# BREAKER_BOARD_FOR_TLC5951.net
KiCad netlist of a schematic drawn in EAGLE
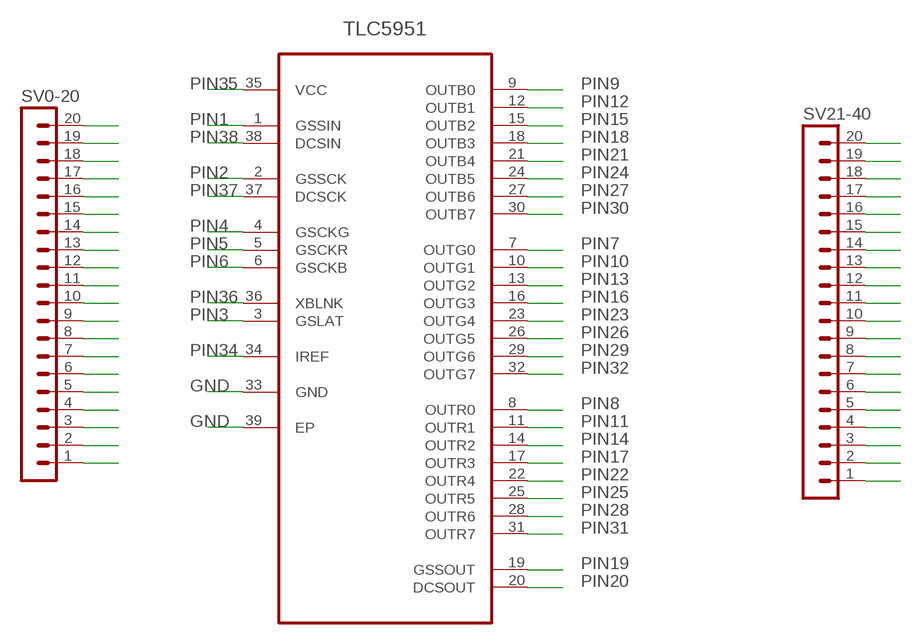
[diagram p0: schematic, sheet 1]

(export (version "E")
  (design (tool "Eeschema 10.0.6"))
  (components
    (comp (ref "SV0-20")
      (value "MA20-1")
      (footprint "eagle-import:MA20-1")
      (libsource (lib "eagle-import") (part "MA20-1"))
    )
    (comp (ref "SV21-40")
      (value "MA20-1")
      (footprint "eagle-import:MA20-1")
      (libsource (lib "eagle-import") (part "MA20-1"))
    )
    (comp (ref "TLC5951")
      (value "TLC5951DAP")
      (footprint "eagle-import:SOP65P810X120-39N")
      (libsource (lib "eagle-import") (part "TLC5951DAP"))
    )
  )
  (nets
    (net (code "1") (name "/GND") (class "Default")
      (node (ref "SV0-20") (pin "20") (pinfunction "20_20") (pintype "passive"))
      (node (ref "TLC5951") (pin "33") (pinfunction "GND_33") (pintype "passive"))
      (node (ref "TLC5951") (pin "39") (pinfunction "EP_39") (pintype "passive"))
    )
    (net (code "2") (name "/PIN1") (class "Default")
      (node (ref "SV0-20") (pin "1") (pinfunction "1_1") (pintype "passive"))
      (node (ref "TLC5951") (pin "1") (pinfunction "GSSIN_1") (pintype "input"))
    )
    (net (code "3") (name "/PIN2") (class "Default")
      (node (ref "SV0-20") (pin "2") (pinfunction "2_2") (pintype "passive"))
      (node (ref "TLC5951") (pin "2") (pinfunction "GSSCK_2") (pintype "input"))
    )
    (net (code "4") (name "/PIN3") (class "Default")
      (node (ref "SV0-20") (pin "3") (pinfunction "3_3") (pintype "passive"))
      (node (ref "TLC5951") (pin "3") (pinfunction "GSLAT_3") (pintype "input"))
    )
    (net (code "5") (name "/PIN4") (class "Default")
      (node (ref "SV0-20") (pin "4") (pinfunction "4_4") (pintype "passive"))
      (node (ref "TLC5951") (pin "4") (pinfunction "GSCKG_4") (pintype "input"))
    )
    (net (code "6") (name "/PIN5") (class "Default")
      (node (ref "SV0-20") (pin "5") (pinfunction "5_5") (pintype "passive"))
      (node (ref "TLC5951") (pin "5") (pinfunction "GSCKR_5") (pintype "input"))
    )
    (net (code "7") (name "/PIN6") (class "Default")
      (node (ref "SV0-20") (pin "6") (pinfunction "6_6") (pintype "passive"))
      (node (ref "TLC5951") (pin "6") (pinfunction "GSCKB_6") (pintype "input"))
    )
    (net (code "8") (name "/PIN7") (class "Default")
      (node (ref "SV0-20") (pin "7") (pinfunction "7_7") (pintype "passive"))
      (node (ref "TLC5951") (pin "7") (pinfunction "OUTG0_7") (pintype "output"))
    )
    (net (code "9") (name "/PIN8") (class "Default")
      (node (ref "SV0-20") (pin "8") (pinfunction "8_8") (pintype "passive"))
      (node (ref "TLC5951") (pin "8") (pinfunction "OUTR0_8") (pintype "output"))
    )
    (net (code "10") (name "/PIN9") (class "Default")
      (node (ref "SV0-20") (pin "9") (pinfunction "9_9") (pintype "passive"))
      (node (ref "TLC5951") (pin "9") (pinfunction "OUTB0_9") (pintype "output"))
    )
    (net (code "11") (name "/PIN10") (class "Default")
      (node (ref "SV0-20") (pin "10") (pinfunction "10_10") (pintype "passive"))
      (node (ref "TLC5951") (pin "10") (pinfunction "OUTG1_10") (pintype "output"))
    )
    (net (code "12") (name "/PIN11") (class "Default")
      (node (ref "SV0-20") (pin "11") (pinfunction "11_11") (pintype "passive"))
      (node (ref "TLC5951") (pin "11") (pinfunction "OUTR1_11") (pintype "output"))
    )
    (net (code "13") (name "/PIN12") (class "Default")
      (node (ref "SV0-20") (pin "12") (pinfunction "12_12") (pintype "passive"))
      (node (ref "TLC5951") (pin "12") (pinfunction "OUTB1_12") (pintype "output"))
    )
    (net (code "14") (name "/PIN13") (class "Default")
      (node (ref "SV0-20") (pin "13") (pinfunction "13_13") (pintype "passive"))
      (node (ref "TLC5951") (pin "13") (pinfunction "OUTG2_13") (pintype "output"))
    )
    (net (code "15") (name "/PIN14") (class "Default")
      (node (ref "SV0-20") (pin "14") (pinfunction "14_14") (pintype "passive"))
      (node (ref "TLC5951") (pin "14") (pinfunction "OUTR2_14") (pintype "output"))
    )
    (net (code "16") (name "/PIN15") (class "Default")
      (node (ref "SV0-20") (pin "15") (pinfunction "15_15") (pintype "passive"))
      (node (ref "TLC5951") (pin "15") (pinfunction "OUTB2_15") (pintype "output"))
    )
    (net (code "17") (name "/PIN16") (class "Default")
      (node (ref "SV0-20") (pin "16") (pinfunction "16_16") (pintype "passive"))
      (node (ref "TLC5951") (pin "16") (pinfunction "OUTG3_16") (pintype "output"))
    )
    (net (code "18") (name "/PIN17") (class "Default")
      (node (ref "SV0-20") (pin "17") (pinfunction "17_17") (pintype "passive"))
      (node (ref "TLC5951") (pin "17") (pinfunction "OUTR3_17") (pintype "output"))
    )
    (net (code "19") (name "/PIN18") (class "Default")
      (node (ref "SV0-20") (pin "18") (pinfunction "18_18") (pintype "passive"))
      (node (ref "TLC5951") (pin "18") (pinfunction "OUTB3_18") (pintype "output"))
    )
    (net (code "20") (name "/PIN19") (class "Default")
      (node (ref "SV0-20") (pin "19") (pinfunction "19_19") (pintype "passive"))
      (node (ref "TLC5951") (pin "19") (pinfunction "GSSOUT_19") (pintype "output"))
    )
    (net (code "21") (name "/PIN20") (class "Default")
      (node (ref "SV21-40") (pin "19") (pinfunction "19_19") (pintype "passive"))
      (node (ref "TLC5951") (pin "20") (pinfunction "DCSOUT_20") (pintype "output"))
    )
    (net (code "22") (name "/PIN21") (class "Default")
      (node (ref "SV21-40") (pin "18") (pinfunction "18_18") (pintype "passive"))
      (node (ref "TLC5951") (pin "21") (pinfunction "OUTB4_21") (pintype "output"))
    )
    (net (code "23") (name "/PIN22") (class "Default")
      (node (ref "SV21-40") (pin "17") (pinfunction "17_17") (pintype "passive"))
      (node (ref "TLC5951") (pin "22") (pinfunction "OUTR4_22") (pintype "output"))
    )
    (net (code "24") (name "/PIN23") (class "Default")
      (node (ref "SV21-40") (pin "16") (pinfunction "16_16") (pintype "passive"))
      (node (ref "TLC5951") (pin "23") (pinfunction "OUTG4_23") (pintype "output"))
    )
    (net (code "25") (name "/PIN24") (class "Default")
      (node (ref "SV21-40") (pin "15") (pinfunction "15_15") (pintype "passive"))
      (node (ref "TLC5951") (pin "24") (pinfunction "OUTB5_24") (pintype "output"))
    )
    (net (code "26") (name "/PIN25") (class "Default")
      (node (ref "SV21-40") (pin "14") (pinfunction "14_14") (pintype "passive"))
      (node (ref "TLC5951") (pin "25") (pinfunction "OUTR5_25") (pintype "output"))
    )
    (net (code "27") (name "/PIN26") (class "Default")
      (node (ref "SV21-40") (pin "13") (pinfunction "13_13") (pintype "passive"))
      (node (ref "TLC5951") (pin "26") (pinfunction "OUTG5_26") (pintype "output"))
    )
    (net (code "28") (name "/PIN27") (class "Default")
      (node (ref "SV21-40") (pin "12") (pinfunction "12_12") (pintype "passive"))
      (node (ref "TLC5951") (pin "27") (pinfunction "OUTB6_27") (pintype "output"))
    )
    (net (code "29") (name "/PIN28") (class "Default")
      (node (ref "SV21-40") (pin "11") (pinfunction "11_11") (pintype "passive"))
      (node (ref "TLC5951") (pin "28") (pinfunction "OUTR6_28") (pintype "output"))
    )
    (net (code "30") (name "/PIN29") (class "Default")
      (node (ref "SV21-40") (pin "10") (pinfunction "10_10") (pintype "passive"))
      (node (ref "TLC5951") (pin "29") (pinfunction "OUTG6_29") (pintype "output"))
    )
    (net (code "31") (name "/PIN30") (class "Default")
      (node (ref "SV21-40") (pin "9") (pinfunction "9_9") (pintype "passive"))
      (node (ref "TLC5951") (pin "30") (pinfunction "OUTB7_30") (pintype "output"))
    )
    (net (code "32") (name "/PIN31") (class "Default")
      (node (ref "SV21-40") (pin "8") (pinfunction "8_8") (pintype "passive"))
      (node (ref "TLC5951") (pin "31") (pinfunction "OUTR7_31") (pintype "output"))
    )
    (net (code "33") (name "/PIN32") (class "Default")
      (node (ref "SV21-40") (pin "7") (pinfunction "7_7") (pintype "passive"))
      (node (ref "TLC5951") (pin "32") (pinfunction "OUTG7_32") (pintype "output"))
    )
    (net (code "34") (name "/PIN34") (class "Default")
      (node (ref "SV21-40") (pin "5") (pinfunction "5_5") (pintype "passive"))
      (node (ref "TLC5951") (pin "34") (pinfunction "IREF_34") (pintype "bidirectional"))
    )
    (net (code "35") (name "/PIN35") (class "Default")
      (node (ref "SV21-40") (pin "4") (pinfunction "4_4") (pintype "passive"))
      (node (ref "TLC5951") (pin "35") (pinfunction "VCC_35") (pintype "power_in"))
    )
    (net (code "36") (name "/PIN36") (class "Default")
      (node (ref "SV21-40") (pin "3") (pinfunction "3_3") (pintype "passive"))
      (node (ref "TLC5951") (pin "36") (pinfunction "XBLNK_36") (pintype "input"))
    )
    (net (code "37") (name "/PIN37") (class "Default")
      (node (ref "SV21-40") (pin "2") (pinfunction "2_2") (pintype "passive"))
      (node (ref "TLC5951") (pin "37") (pinfunction "DCSCK_37") (pintype "input"))
    )
    (net (code "38") (name "/PIN38") (class "Default")
      (node (ref "SV21-40") (pin "1") (pinfunction "1_1") (pintype "passive"))
      (node (ref "TLC5951") (pin "38") (pinfunction "DCSIN_38") (pintype "input"))
    )
    (net (code "39") (name "unconnected-(SV21-40-Pad6)") (class "Default")
      (node (ref "SV21-40") (pin "6") (pinfunction "6_6") (pintype "passive"))
    )
    (net (code "40") (name "unconnected-(SV21-40-Pad20)") (class "Default")
      (node (ref "SV21-40") (pin "20") (pinfunction "20_20") (pintype "passive"))
    )
  )
)
